# amplifier_only_clean.net
KiCad netlist of a schematic drawn in EAGLE
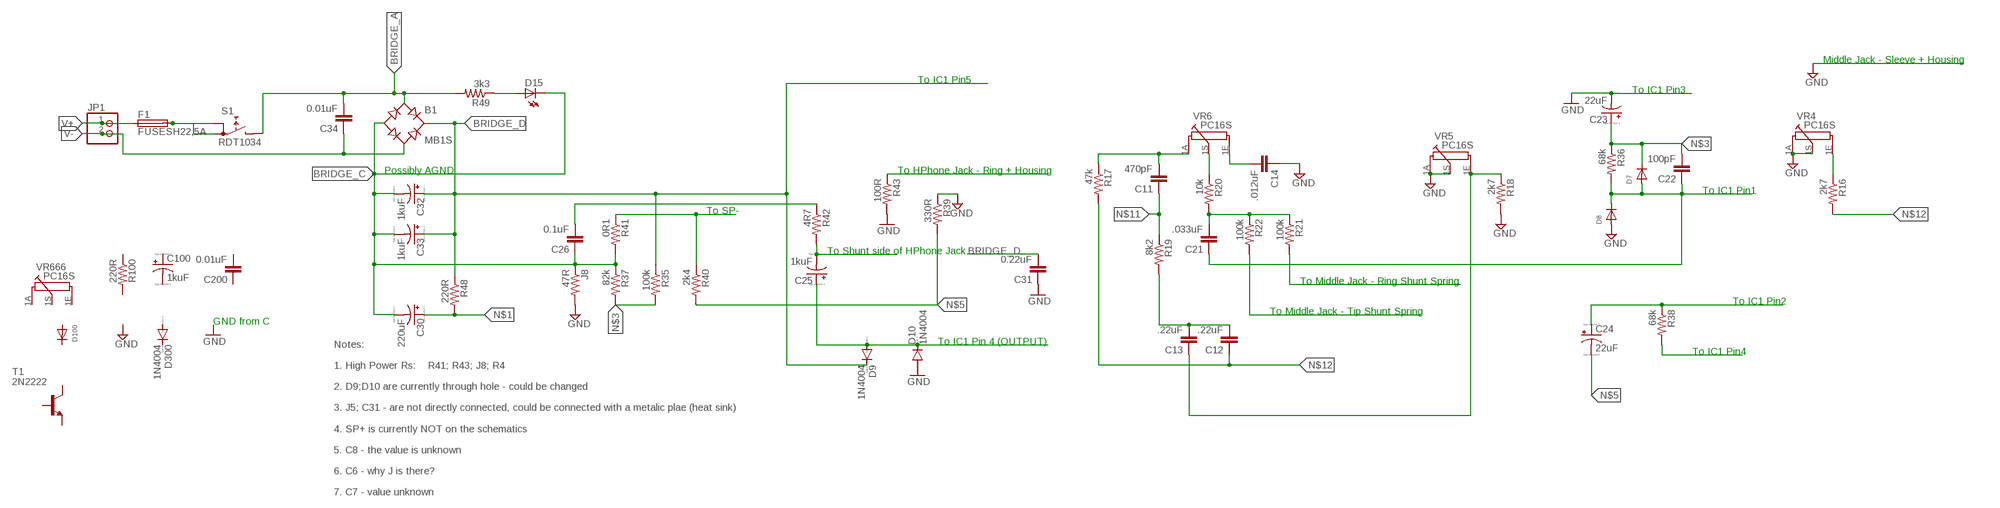
[diagram p0: schematic, sheet 1, part 1 of 2]
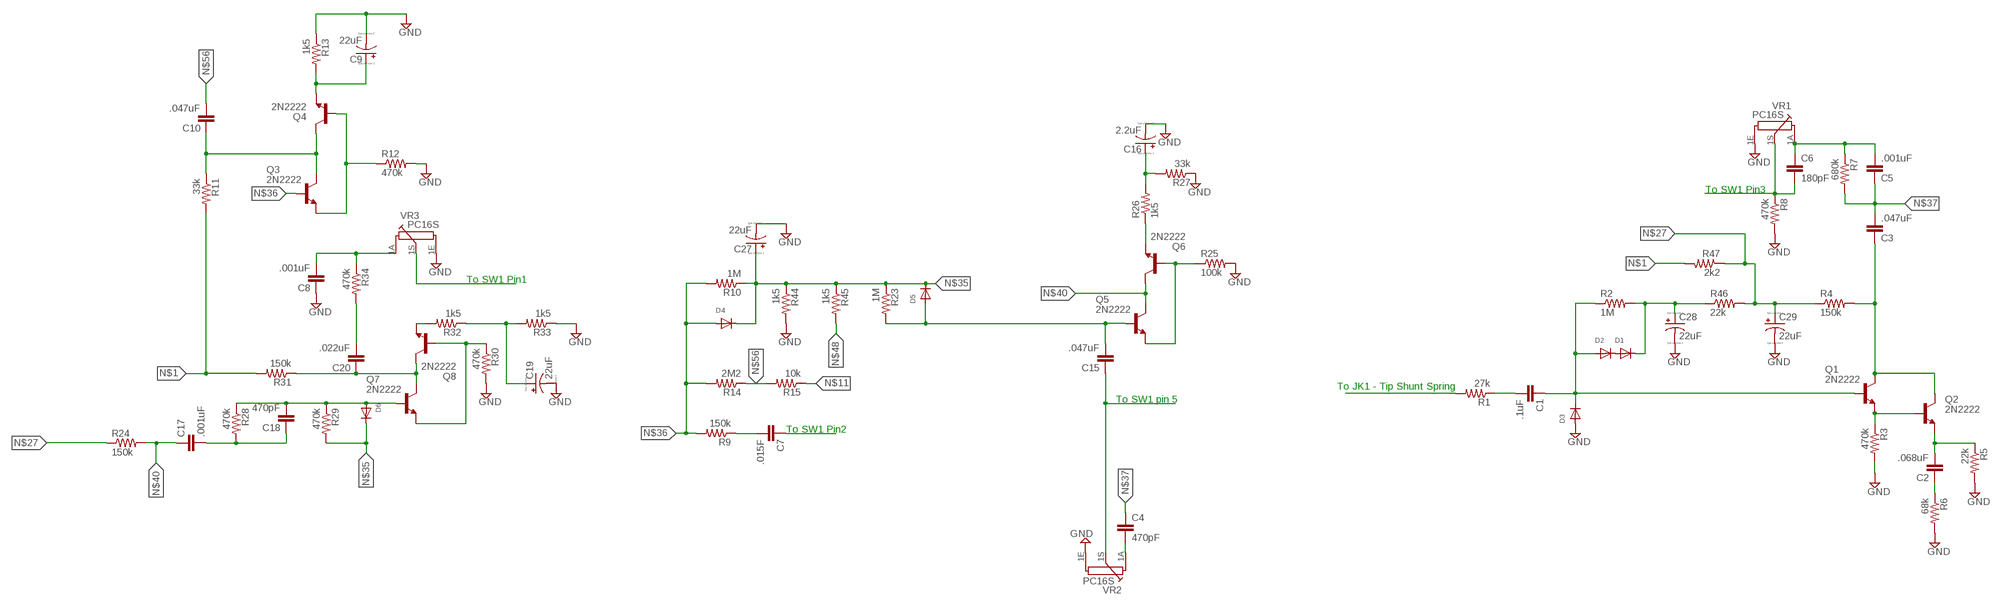
[diagram p1: schematic, sheet 1, part 2 of 2]

(export (version "E")
  (design (tool "Eeschema 10.0.6"))
  (components
    (comp (ref "B1")
      (value "MB1S")
      (footprint "eagle-import:SOIC-4")
      (libsource (lib "eagle-import") (part "MBS1"))
    )
    (comp (ref "C1")
      (value ".1uF")
      (footprint "eagle-import:C0603")
      (libsource (lib "eagle-import") (part "C-EUC0603"))
    )
    (comp (ref "C2")
      (value ".068uF")
      (footprint "eagle-import:C0603")
      (libsource (lib "eagle-import") (part "C-EUC0603"))
    )
    (comp (ref "C3")
      (value ".047uF")
      (footprint "eagle-import:C0603")
      (libsource (lib "eagle-import") (part "C-EUC0603"))
    )
    (comp (ref "C4")
      (value "470pF")
      (footprint "eagle-import:C0603")
      (libsource (lib "eagle-import") (part "C-EUC0603"))
    )
    (comp (ref "C5")
      (value ".001uF")
      (footprint "eagle-import:C0603")
      (libsource (lib "eagle-import") (part "C-EUC0603"))
    )
    (comp (ref "C6")
      (value "180pF")
      (footprint "eagle-import:C0603")
      (libsource (lib "eagle-import") (part "C-EUC0603"))
    )
    (comp (ref "C7")
      (value ".015F")
      (footprint "eagle-import:C0603")
      (libsource (lib "eagle-import") (part "C-EUC0603"))
    )
    (comp (ref "C8")
      (value ".001uF")
      (footprint "eagle-import:C0603")
      (libsource (lib "eagle-import") (part "C-EUC0603"))
    )
    (comp (ref "C9")
      (value "22uF")
      (footprint "eagle-import:EB30D")
      (libsource (lib "eagle-import") (part "CPOL-USE10-30"))
    )
    (comp (ref "C10")
      (value ".047uF")
      (footprint "eagle-import:C0603")
      (libsource (lib "eagle-import") (part "C-EUC0603"))
    )
    (comp (ref "C11")
      (value "470pF")
      (footprint "eagle-import:C0603")
      (libsource (lib "eagle-import") (part "C-EUC0603"))
    )
    (comp (ref "C12")
      (value ".22uF")
      (footprint "eagle-import:C0603")
      (libsource (lib "eagle-import") (part "C-EUC0603"))
    )
    (comp (ref "C13")
      (value ".22uF")
      (footprint "eagle-import:C0603")
      (libsource (lib "eagle-import") (part "C-EUC0603"))
    )
    (comp (ref "C14")
      (value ".012uF")
      (footprint "eagle-import:C0603")
      (libsource (lib "eagle-import") (part "C-EUC0603"))
    )
    (comp (ref "C15")
      (value ".047uF")
      (footprint "eagle-import:C0603")
      (libsource (lib "eagle-import") (part "C-EUC0603"))
    )
    (comp (ref "C16")
      (value "2.2uF")
      (footprint "eagle-import:EB30D")
      (libsource (lib "eagle-import") (part "CPOL-USE10-30"))
    )
    (comp (ref "C17")
      (value ".001uF")
      (footprint "eagle-import:C0603")
      (libsource (lib "eagle-import") (part "C-EUC0603"))
    )
    (comp (ref "C18")
      (value "470pF")
      (footprint "eagle-import:C0603")
      (libsource (lib "eagle-import") (part "C-EUC0603"))
    )
    (comp (ref "C19")
      (value "22uF")
      (footprint "eagle-import:EB30D")
      (libsource (lib "eagle-import") (part "CPOL-USE10-30"))
    )
    (comp (ref "C20")
      (value ".022uF")
      (footprint "eagle-import:C0603")
      (libsource (lib "eagle-import") (part "C-EUC0603"))
    )
    (comp (ref "C21")
      (value ".033uF")
      (footprint "eagle-import:C0603")
      (libsource (lib "eagle-import") (part "C-EUC0603"))
    )
    (comp (ref "C22")
      (value "100pF")
      (footprint "eagle-import:C0603")
      (libsource (lib "eagle-import") (part "C-EUC0603"))
    )
    (comp (ref "C23")
      (value "22uF")
      (footprint "eagle-import:EB30D")
      (libsource (lib "eagle-import") (part "CPOL-USE10-30"))
    )
    (comp (ref "C24")
      (value "22uF")
      (footprint "eagle-import:EB30D")
      (libsource (lib "eagle-import") (part "CPOL-USE10-30"))
    )
    (comp (ref "C25")
      (value "1kuF")
      (footprint "eagle-import:EB30D")
      (libsource (lib "eagle-import") (part "CPOL-USE10-30"))
    )
    (comp (ref "C26")
      (value "0.1uF")
      (footprint "eagle-import:C0603")
      (libsource (lib "eagle-import") (part "C-EUC0603"))
    )
    (comp (ref "C27")
      (value "22uF")
      (footprint "eagle-import:EB30D")
      (libsource (lib "eagle-import") (part "CPOL-USE10-30"))
    )
    (comp (ref "C28")
      (value "22uF")
      (footprint "eagle-import:EB30D")
      (libsource (lib "eagle-import") (part "CPOL-USE10-30"))
    )
    (comp (ref "C29")
      (value "22uF")
      (footprint "eagle-import:EB30D")
      (libsource (lib "eagle-import") (part "CPOL-USE10-30"))
    )
    (comp (ref "C30")
      (value "220uF")
      (footprint "eagle-import:E3,5-8")
      (libsource (lib "eagle-import") (part "CPOL-USE3.5-8"))
    )
    (comp (ref "C31")
      (value "0.22uF")
      (footprint "eagle-import:C0603")
      (libsource (lib "eagle-import") (part "C-EUC0603"))
    )
    (comp (ref "C32")
      (value "1kuF")
      (footprint "eagle-import:EB30D")
      (libsource (lib "eagle-import") (part "CPOL-USE10-30"))
    )
    (comp (ref "C33")
      (value "1kuF")
      (footprint "eagle-import:EB30D")
      (libsource (lib "eagle-import") (part "CPOL-USE10-30"))
    )
    (comp (ref "C34")
      (value "0.01uF")
      (footprint "eagle-import:C0603")
      (libsource (lib "eagle-import") (part "C-EUC0603"))
    )
    (comp (ref "C100")
      (value "1kuF")
      (footprint "eagle-import:EB30D")
      (libsource (lib "eagle-import") (part "CPOL-USE10-30"))
    )
    (comp (ref "C200")
      (value "0.01uF")
      (footprint "eagle-import:C0603")
      (libsource (lib "eagle-import") (part "C-EUC0603"))
    )
    (comp (ref "D1")
      (value "DIODESOD-323F")
      (footprint "eagle-import:SOD-323F")
      (libsource (lib "eagle-import") (part "DIODESOD-323F"))
    )
    (comp (ref "D2")
      (value "DIODESOD-323F")
      (footprint "eagle-import:SOD-323F")
      (libsource (lib "eagle-import") (part "DIODESOD-323F"))
    )
    (comp (ref "D3")
      (value "DIODESOD-323F")
      (footprint "eagle-import:SOD-323F")
      (libsource (lib "eagle-import") (part "DIODESOD-323F"))
    )
    (comp (ref "D4")
      (value "DIODESOD-323F")
      (footprint "eagle-import:SOD-323F")
      (libsource (lib "eagle-import") (part "DIODESOD-323F"))
    )
    (comp (ref "D5")
      (value "DIODESOD-323F")
      (footprint "eagle-import:SOD-323F")
      (libsource (lib "eagle-import") (part "DIODESOD-323F"))
    )
    (comp (ref "D6")
      (value "DIODESOD-323F")
      (footprint "eagle-import:SOD-323F")
      (libsource (lib "eagle-import") (part "DIODESOD-323F"))
    )
    (comp (ref "D7")
      (value "DIODESOD-323F")
      (footprint "eagle-import:SOD-323F")
      (libsource (lib "eagle-import") (part "DIODESOD-323F"))
    )
    (comp (ref "D8")
      (value "DIODESOD-323F")
      (footprint "eagle-import:SOD-323F")
      (libsource (lib "eagle-import") (part "DIODESOD-323F"))
    )
    (comp (ref "D9")
      (value "1N4004")
      (footprint "eagle-import:DO41-10")
      (libsource (lib "eagle-import") (part "1N4004"))
    )
    (comp (ref "D10")
      (value "1N4004")
      (footprint "eagle-import:DO41-10")
      (libsource (lib "eagle-import") (part "1N4004"))
    )
    (comp (ref "D15")
      (value "LEDCHIP-LED0603")
      (footprint "eagle-import:CHIP-LED0603")
      (libsource (lib "eagle-import") (part "LEDCHIP-LED0603"))
    )
    (comp (ref "D100")
      (value "DIODESOD-323F")
      (footprint "eagle-import:SOD-323F")
      (libsource (lib "eagle-import") (part "DIODESOD-323F"))
    )
    (comp (ref "D300")
      (value "1N4004")
      (footprint "eagle-import:DO41-10")
      (libsource (lib "eagle-import") (part "1N4004"))
    )
    (comp (ref "F1")
      (value "FUSESH22,5A")
      (footprint "eagle-import:SH22,5A")
      (libsource (lib "eagle-import") (part "FUSESH22,5A"))
    )
    (comp (ref "J8")
      (value "47R")
      (footprint "eagle-import:R0603")
      (libsource (lib "eagle-import") (part "R-US_R0603"))
    )
    (comp (ref "JP1")
      (value "PINHD-1X2")
      (footprint "eagle-import:1X02")
      (libsource (lib "eagle-import") (part "PINHD-1X2"))
    )
    (comp (ref "Q1")
      (value "2N2222")
      (footprint "eagle-import:TO92-EBC-OVAL")
      (libsource (lib "eagle-import") (part "2N2222"))
    )
    (comp (ref "Q2")
      (value "2N2222")
      (footprint "eagle-import:TO92-EBC-OVAL")
      (libsource (lib "eagle-import") (part "2N2222"))
    )
    (comp (ref "Q3")
      (value "2N2222")
      (footprint "eagle-import:TO92-EBC-OVAL")
      (libsource (lib "eagle-import") (part "2N2222"))
    )
    (comp (ref "Q4")
      (value "2N2222")
      (footprint "eagle-import:TO92-EBC-OVAL")
      (libsource (lib "eagle-import") (part "2N2222"))
    )
    (comp (ref "Q5")
      (value "2N2222")
      (footprint "eagle-import:TO92-EBC-OVAL")
      (libsource (lib "eagle-import") (part "2N2222"))
    )
    (comp (ref "Q6")
      (value "2N2222")
      (footprint "eagle-import:TO92-EBC-OVAL")
      (libsource (lib "eagle-import") (part "2N2222"))
    )
    (comp (ref "Q7")
      (value "2N2222")
      (footprint "eagle-import:TO92-EBC-OVAL")
      (libsource (lib "eagle-import") (part "2N2222"))
    )
    (comp (ref "Q8")
      (value "2N2222")
      (footprint "eagle-import:TO92-EBC-OVAL")
      (libsource (lib "eagle-import") (part "2N2222"))
    )
    (comp (ref "R1")
      (value "27k")
      (footprint "eagle-import:R0603")
      (libsource (lib "eagle-import") (part "R-US_R0603"))
    )
    (comp (ref "R2")
      (value "1M")
      (footprint "eagle-import:R0603")
      (libsource (lib "eagle-import") (part "R-US_R0603"))
    )
    (comp (ref "R3")
      (value "470k")
      (footprint "eagle-import:R0603")
      (libsource (lib "eagle-import") (part "R-US_R0603"))
    )
    (comp (ref "R4")
      (value "150k")
      (footprint "eagle-import:R0603")
      (libsource (lib "eagle-import") (part "R-US_R0603"))
    )
    (comp (ref "R5")
      (value "22k")
      (footprint "eagle-import:R0603")
      (libsource (lib "eagle-import") (part "R-US_R0603"))
    )
    (comp (ref "R6")
      (value "68k")
      (footprint "eagle-import:R0603")
      (libsource (lib "eagle-import") (part "R-US_R0603"))
    )
    (comp (ref "R7")
      (value "680k")
      (footprint "eagle-import:R0603")
      (libsource (lib "eagle-import") (part "R-US_R0603"))
    )
    (comp (ref "R8")
      (value "470k")
      (footprint "eagle-import:R0603")
      (libsource (lib "eagle-import") (part "R-US_R0603"))
    )
    (comp (ref "R9")
      (value "150k")
      (footprint "eagle-import:R0603")
      (libsource (lib "eagle-import") (part "R-US_R0603"))
    )
    (comp (ref "R10")
      (value "1M")
      (footprint "eagle-import:R0603")
      (libsource (lib "eagle-import") (part "R-US_R0603"))
    )
    (comp (ref "R11")
      (value "33k")
      (footprint "eagle-import:R0603")
      (libsource (lib "eagle-import") (part "R-US_R0603"))
    )
    (comp (ref "R12")
      (value "470k")
      (footprint "eagle-import:R0603")
      (libsource (lib "eagle-import") (part "R-US_R0603"))
    )
    (comp (ref "R13")
      (value "1k5")
      (footprint "eagle-import:R0603")
      (libsource (lib "eagle-import") (part "R-US_R0603"))
    )
    (comp (ref "R14")
      (value "2M2")
      (footprint "eagle-import:R0603")
      (libsource (lib "eagle-import") (part "R-US_R0603"))
    )
    (comp (ref "R15")
      (value "10k")
      (footprint "eagle-import:R0603")
      (libsource (lib "eagle-import") (part "R-US_R0603"))
    )
    (comp (ref "R16")
      (value "2k7")
      (footprint "eagle-import:R0603")
      (libsource (lib "eagle-import") (part "R-US_R0603"))
    )
    (comp (ref "R17")
      (value "47k")
      (footprint "eagle-import:R0603")
      (libsource (lib "eagle-import") (part "R-US_R0603"))
    )
    (comp (ref "R18")
      (value "2k7")
      (footprint "eagle-import:R0603")
      (libsource (lib "eagle-import") (part "R-US_R0603"))
    )
    (comp (ref "R19")
      (value "8k2")
      (footprint "eagle-import:R0603")
      (libsource (lib "eagle-import") (part "R-US_R0603"))
    )
    (comp (ref "R20")
      (value "10k")
      (footprint "eagle-import:R0603")
      (libsource (lib "eagle-import") (part "R-US_R0603"))
    )
    (comp (ref "R21")
      (value "100k")
      (footprint "eagle-import:R0603")
      (libsource (lib "eagle-import") (part "R-US_R0603"))
    )
    (comp (ref "R22")
      (value "100k")
      (footprint "eagle-import:R0603")
      (libsource (lib "eagle-import") (part "R-US_R0603"))
    )
    (comp (ref "R23")
      (value "1M")
      (footprint "eagle-import:R0603")
      (libsource (lib "eagle-import") (part "R-US_R0603"))
    )
    (comp (ref "R24")
      (value "150k")
      (footprint "eagle-import:R0603")
      (libsource (lib "eagle-import") (part "R-US_R0603"))
    )
    (comp (ref "R25")
      (value "100k")
      (footprint "eagle-import:R0603")
      (libsource (lib "eagle-import") (part "R-US_R0603"))
    )
    (comp (ref "R26")
      (value "1k5")
      (footprint "eagle-import:R0603")
      (libsource (lib "eagle-import") (part "R-US_R0603"))
    )
    (comp (ref "R27")
      (value "33k")
      (footprint "eagle-import:R0603")
      (libsource (lib "eagle-import") (part "R-US_R0603"))
    )
    (comp (ref "R28")
      (value "470k")
      (footprint "eagle-import:R0603")
      (libsource (lib "eagle-import") (part "R-US_R0603"))
    )
    (comp (ref "R29")
      (value "470k")
      (footprint "eagle-import:R0603")
      (libsource (lib "eagle-import") (part "R-US_R0603"))
    )
    (comp (ref "R30")
      (value "470k")
      (footprint "eagle-import:R0603")
      (libsource (lib "eagle-import") (part "R-US_R0603"))
    )
    (comp (ref "R31")
      (value "150k")
      (footprint "eagle-import:R0603")
      (libsource (lib "eagle-import") (part "R-US_R0603"))
    )
    (comp (ref "R32")
      (value "1k5")
      (footprint "eagle-import:R0603")
      (libsource (lib "eagle-import") (part "R-US_R0603"))
    )
    (comp (ref "R33")
      (value "1k5")
      (footprint "eagle-import:R0603")
      (libsource (lib "eagle-import") (part "R-US_R0603"))
    )
    (comp (ref "R34")
      (value "470k")
      (footprint "eagle-import:R0603")
      (libsource (lib "eagle-import") (part "R-US_R0603"))
    )
    (comp (ref "R35")
      (value "100k")
      (footprint "eagle-import:R0603")
      (libsource (lib "eagle-import") (part "R-US_R0603"))
    )
    (comp (ref "R36")
      (value "68k")
      (footprint "eagle-import:R0603")
      (libsource (lib "eagle-import") (part "R-US_R0603"))
    )
    (comp (ref "R37")
      (value "82k")
      (footprint "eagle-import:R0603")
      (libsource (lib "eagle-import") (part "R-US_R0603"))
    )
    (comp (ref "R38")
      (value "68k")
      (footprint "eagle-import:R0603")
      (libsource (lib "eagle-import") (part "R-US_R0603"))
    )
    (comp (ref "R39")
      (value "330R")
      (footprint "eagle-import:R0603")
      (libsource (lib "eagle-import") (part "R-US_R0603"))
    )
    (comp (ref "R40")
      (value "2k4")
      (footprint "eagle-import:R0603")
      (libsource (lib "eagle-import") (part "R-US_R0603"))
    )
    (comp (ref "R41")
      (value "0R1")
      (footprint "eagle-import:R0603")
      (libsource (lib "eagle-import") (part "R-US_R0603"))
    )
    (comp (ref "R42")
      (value "4R7")
      (footprint "eagle-import:R0603")
      (libsource (lib "eagle-import") (part "R-US_R0603"))
    )
    (comp (ref "R43")
      (value "100R")
      (footprint "eagle-import:R0603")
      (libsource (lib "eagle-import") (part "R-US_R0603"))
    )
    (comp (ref "R44")
      (value "1k5")
      (footprint "eagle-import:R0603")
      (libsource (lib "eagle-import") (part "R-US_R0603"))
    )
    (comp (ref "R45")
      (value "1k5")
      (footprint "eagle-import:R0603")
      (libsource (lib "eagle-import") (part "R-US_R0603"))
    )
    (comp (ref "R46")
      (value "22k")
      (footprint "eagle-import:R0603")
      (libsource (lib "eagle-import") (part "R-US_R0603"))
    )
    (comp (ref "R47")
      (value "2k2")
      (footprint "eagle-import:R0603")
      (libsource (lib "eagle-import") (part "R-US_R0603"))
    )
    (comp (ref "R48")
      (value "220R")
      (footprint "eagle-import:R0603")
      (libsource (lib "eagle-import") (part "R-US_R0603"))
    )
    (comp (ref "R49")
      (value "3k3")
      (footprint "eagle-import:R0603")
      (libsource (lib "eagle-import") (part "R-US_R0603"))
    )
    (comp (ref "R100")
      (value "220R")
      (footprint "eagle-import:R0603")
      (libsource (lib "eagle-import") (part "R-US_R0603"))
    )
    (comp (ref "S1")
      (value "RDT1034")
      (footprint "eagle-import:RDT1034")
      (libsource (lib "eagle-import") (part "RDT1034"))
    )
    (comp (ref "T1")
      (value "2N2222")
      (footprint "eagle-import:TO92-EBC-OVAL")
      (libsource (lib "eagle-import") (part "2N2222"))
    )
    (comp (ref "VR1")
      (value "PC16S")
      (footprint "eagle-import:PC16S")
      (libsource (lib "eagle-import") (part "PC16S"))
    )
    (comp (ref "VR2")
      (value "PC16S")
      (footprint "eagle-import:PC16S")
      (libsource (lib "eagle-import") (part "PC16S"))
    )
    (comp (ref "VR3")
      (value "PC16S")
      (footprint "eagle-import:PC16S")
      (libsource (lib "eagle-import") (part "PC16S"))
    )
    (comp (ref "VR4")
      (value "PC16S")
      (footprint "eagle-import:PC16S")
      (libsource (lib "eagle-import") (part "PC16S"))
    )
    (comp (ref "VR5")
      (value "PC16S")
      (footprint "eagle-import:PC16S")
      (libsource (lib "eagle-import") (part "PC16S"))
    )
    (comp (ref "VR6")
      (value "PC16S")
      (footprint "eagle-import:PC16S")
      (libsource (lib "eagle-import") (part "PC16S"))
    )
    (comp (ref "VR666")
      (value "PC16S")
      (footprint "eagle-import:PC16S")
      (libsource (lib "eagle-import") (part "PC16S"))
    )
  )
  (nets
    (net (code "1") (name "BRIDGE_A") (class "Default")
      (node (ref "B1") (pin "~1") (pinfunction "AC1_~1") (pintype "passive"))
      (node (ref "C34") (pin "2") (pinfunction "2_2") (pintype "passive"))
      (node (ref "R49") (pin "2") (pinfunction "2_2") (pintype "passive"))
      (node (ref "S1") (pin "B") (pinfunction "B_B") (pintype "passive"))
    )
    (net (code "2") (name "BRIDGE_C") (class "Default")
      (node (ref "B1") (pin "-") (pinfunction "-_-") (pintype "passive"))
      (node (ref "C26") (pin "1") (pinfunction "1_1") (pintype "passive"))
      (node (ref "C30") (pin "-") (pinfunction "-_-") (pintype "passive"))
      (node (ref "C32") (pin "-") (pinfunction "-_-") (pintype "passive"))
      (node (ref "C33") (pin "-") (pinfunction "-_-") (pintype "passive"))
      (node (ref "D15") (pin "C") (pinfunction "C_C") (pintype "passive"))
      (node (ref "J8") (pin "1") (pinfunction "1_1") (pintype "passive"))
      (node (ref "R37") (pin "1") (pinfunction "1_1") (pintype "passive"))
      (node (ref "R41") (pin "2") (pinfunction "2_2") (pintype "passive"))
    )
    (net (code "3") (name "BRIDGE_D") (class "Default")
      (node (ref "B1") (pin "+") (pinfunction "+_+") (pintype "passive"))
      (node (ref "C31") (pin "2") (pinfunction "2_2") (pintype "passive"))
      (node (ref "C32") (pin "+") (pinfunction "+_+") (pintype "passive"))
      (node (ref "C33") (pin "+") (pinfunction "+_+") (pintype "passive"))
      (node (ref "D9") (pin "C") (pinfunction "C_C") (pintype "passive"))
      (node (ref "R35") (pin "1") (pinfunction "1_1") (pintype "passive"))
      (node (ref "R48") (pin "1") (pinfunction "1_1") (pintype "passive"))
    )
    (net (code "4") (name "GND") (class "Default")
      (node (ref "C14") (pin "1") (pinfunction "1_1") (pintype "passive"))
      (node (ref "C16") (pin "-") (pinfunction "-_-") (pintype "passive"))
      (node (ref "C19") (pin "-") (pinfunction "-_-") (pintype "passive"))
      (node (ref "C23") (pin "-") (pinfunction "-_-") (pintype "passive"))
      (node (ref "C27") (pin "-") (pinfunction "-_-") (pintype "passive"))
      (node (ref "C28") (pin "-") (pinfunction "-_-") (pintype "passive"))
      (node (ref "C29") (pin "-") (pinfunction "-_-") (pintype "passive"))
      (node (ref "C31") (pin "1") (pinfunction "1_1") (pintype "passive"))
      (node (ref "C8") (pin "1") (pinfunction "1_1") (pintype "passive"))
      (node (ref "C9") (pin "-") (pinfunction "-_-") (pintype "passive"))
      (node (ref "D10") (pin "A") (pinfunction "A_A") (pintype "passive"))
      (node (ref "D3") (pin "A") (pinfunction "A_A") (pintype "passive"))
      (node (ref "D8") (pin "A") (pinfunction "A_A") (pintype "passive"))
      (node (ref "J8") (pin "2") (pinfunction "2_2") (pintype "passive"))
      (node (ref "R12") (pin "2") (pinfunction "2_2") (pintype "passive"))
      (node (ref "R13") (pin "1") (pinfunction "1_1") (pintype "passive"))
      (node (ref "R18") (pin "2") (pinfunction "2_2") (pintype "passive"))
      (node (ref "R25") (pin "2") (pinfunction "2_2") (pintype "passive"))
      (node (ref "R27") (pin "1") (pinfunction "1_1") (pintype "passive"))
      (node (ref "R3") (pin "2") (pinfunction "2_2") (pintype "passive"))
      (node (ref "R30") (pin "2") (pinfunction "2_2") (pintype "passive"))
      (node (ref "R33") (pin "1") (pinfunction "1_1") (pintype "passive"))
      (node (ref "R39") (pin "1") (pinfunction "1_1") (pintype "passive"))
      (node (ref "R43") (pin "2") (pinfunction "2_2") (pintype "passive"))
      (node (ref "R44") (pin "2") (pinfunction "2_2") (pintype "passive"))
      (node (ref "R5") (pin "2") (pinfunction "2_2") (pintype "passive"))
      (node (ref "R6") (pin "2") (pinfunction "2_2") (pintype "passive"))
      (node (ref "R8") (pin "2") (pinfunction "2_2") (pintype "passive"))
      (node (ref "VR1") (pin "1E") (pinfunction "1E_1E") (pintype "passive"))
      (node (ref "VR2") (pin "1E") (pinfunction "1E_1E") (pintype "passive"))
      (node (ref "VR3") (pin "1E") (pinfunction "1E_1E") (pintype "passive"))
      (node (ref "VR4") (pin "1A") (pinfunction "1A_1A") (pintype "passive"))
      (node (ref "VR4") (pin "1S") (pinfunction "1S_1S") (pintype "passive"))
      (node (ref "VR5") (pin "1A") (pinfunction "1A_1A") (pintype "passive"))
      (node (ref "VR5") (pin "1S") (pinfunction "1S_1S") (pintype "passive"))
    )
    (net (code "5") (name "N$1") (class "Default")
      (node (ref "C30") (pin "+") (pinfunction "+_+") (pintype "passive"))
      (node (ref "R11") (pin "2") (pinfunction "2_2") (pintype "passive"))
      (node (ref "R31") (pin "2") (pinfunction "2_2") (pintype "passive"))
      (node (ref "R47") (pin "2") (pinfunction "2_2") (pintype "passive"))
      (node (ref "R48") (pin "2") (pinfunction "2_2") (pintype "passive"))
    )
    (net (code "6") (name "N$3") (class "Default")
      (node (ref "C22") (pin "2") (pinfunction "2_2") (pintype "passive"))
      (node (ref "C23") (pin "+") (pinfunction "+_+") (pintype "passive"))
      (node (ref "D7") (pin "C") (pinfunction "C_C") (pintype "passive"))
      (node (ref "R35") (pin "2") (pinfunction "2_2") (pintype "passive"))
      (node (ref "R36") (pin "1") (pinfunction "1_1") (pintype "passive"))
      (node (ref "R37") (pin "2") (pinfunction "2_2") (pintype "passive"))
    )
    (net (code "7") (name "N$5") (class "Default")
      (node (ref "C24") (pin "-") (pinfunction "-_-") (pintype "passive"))
      (node (ref "R39") (pin "2") (pinfunction "2_2") (pintype "passive"))
      (node (ref "R40") (pin "2") (pinfunction "2_2") (pintype "passive"))
    )
    (net (code "8") (name "N$11") (class "Default")
      (node (ref "C11") (pin "1") (pinfunction "1_1") (pintype "passive"))
      (node (ref "R15") (pin "1") (pinfunction "1_1") (pintype "passive"))
      (node (ref "R19") (pin "1") (pinfunction "1_1") (pintype "passive"))
    )
    (net (code "9") (name "N$12") (class "Default")
      (node (ref "C12") (pin "1") (pinfunction "1_1") (pintype "passive"))
      (node (ref "R16") (pin "2") (pinfunction "2_2") (pintype "passive"))
      (node (ref "R17") (pin "2") (pinfunction "2_2") (pintype "passive"))
    )
    (net (code "10") (name "N$27") (class "Default")
      (node (ref "C29") (pin "+") (pinfunction "+_+") (pintype "passive"))
      (node (ref "R24") (pin "1") (pinfunction "1_1") (pintype "passive"))
      (node (ref "R4") (pin "1") (pinfunction "1_1") (pintype "passive"))
      (node (ref "R46") (pin "2") (pinfunction "2_2") (pintype "passive"))
      (node (ref "R47") (pin "1") (pinfunction "1_1") (pintype "passive"))
    )
    (net (code "11") (name "N$35") (class "Default")
      (node (ref "C27") (pin "+") (pinfunction "+_+") (pintype "passive"))
      (node (ref "D4") (pin "C") (pinfunction "C_C") (pintype "passive"))
      (node (ref "D5") (pin "C") (pinfunction "C_C") (pintype "passive"))
      (node (ref "D6") (pin "C") (pinfunction "C_C") (pintype "passive"))
      (node (ref "R10") (pin "1") (pinfunction "1_1") (pintype "passive"))
      (node (ref "R23") (pin "1") (pinfunction "1_1") (pintype "passive"))
      (node (ref "R29") (pin "2") (pinfunction "2_2") (pintype "passive"))
      (node (ref "R44") (pin "1") (pinfunction "1_1") (pintype "passive"))
      (node (ref "R45") (pin "1") (pinfunction "1_1") (pintype "passive"))
    )
    (net (code "12") (name "N$36") (class "Default")
      (node (ref "D4") (pin "A") (pinfunction "A_A") (pintype "passive"))
      (node (ref "Q3") (pin "B") (pinfunction "B_B") (pintype "passive"))
      (node (ref "R10") (pin "2") (pinfunction "2_2") (pintype "passive"))
      (node (ref "R14") (pin "2") (pinfunction "2_2") (pintype "passive"))
      (node (ref "R9") (pin "2") (pinfunction "2_2") (pintype "passive"))
    )
    (net (code "13") (name "N$37") (class "Default")
      (node (ref "C3") (pin "2") (pinfunction "2_2") (pintype "passive"))
      (node (ref "C4") (pin "1") (pinfunction "1_1") (pintype "passive"))
      (node (ref "C5") (pin "1") (pinfunction "1_1") (pintype "passive"))
      (node (ref "R7") (pin "2") (pinfunction "2_2") (pintype "passive"))
    )
    (net (code "14") (name "N$40") (class "Default")
      (node (ref "C17") (pin "1") (pinfunction "1_1") (pintype "passive"))
      (node (ref "Q5") (pin "C") (pinfunction "C_C") (pintype "passive"))
      (node (ref "Q6") (pin "C") (pinfunction "C_C") (pintype "passive"))
      (node (ref "R24") (pin "2") (pinfunction "2_2") (pintype "passive"))
    )
    (net (code "15") (name "N$48") (class "Default")
      (node (ref "R45") (pin "2") (pinfunction "2_2") (pintype "passive"))
    )
    (net (code "16") (name "N$56") (class "Default")
      (node (ref "C10") (pin "2") (pinfunction "2_2") (pintype "passive"))
      (node (ref "R14") (pin "1") (pinfunction "1_1") (pintype "passive"))
      (node (ref "R15") (pin "2") (pinfunction "2_2") (pintype "passive"))
    )
    (net (code "17") (name "Net-(C1-Pad1)") (class "Default")
      (node (ref "C1") (pin "1") (pinfunction "1_1") (pintype "passive"))
      (node (ref "D2") (pin "A") (pinfunction "A_A") (pintype "passive"))
      (node (ref "D3") (pin "C") (pinfunction "C_C") (pintype "passive"))
      (node (ref "Q1") (pin "B") (pinfunction "B_B") (pintype "passive"))
      (node (ref "R2") (pin "1") (pinfunction "1_1") (pintype "passive"))
    )
    (net (code "18") (name "Net-(C1-Pad2)") (class "Default")
      (node (ref "C1") (pin "2") (pinfunction "2_2") (pintype "passive"))
      (node (ref "R1") (pin "1") (pinfunction "1_1") (pintype "passive"))
    )
    (net (code "19") (name "Net-(C2-Pad1)") (class "Default")
      (node (ref "C2") (pin "1") (pinfunction "1_1") (pintype "passive"))
      (node (ref "R6") (pin "1") (pinfunction "1_1") (pintype "passive"))
    )
    (net (code "20") (name "Net-(C2-Pad2)") (class "Default")
      (node (ref "C2") (pin "2") (pinfunction "2_2") (pintype "passive"))
      (node (ref "Q2") (pin "E") (pinfunction "E_E") (pintype "passive"))
      (node (ref "R5") (pin "1") (pinfunction "1_1") (pintype "passive"))
    )
    (net (code "21") (name "Net-(C3-Pad1)") (class "Default")
      (node (ref "C3") (pin "1") (pinfunction "1_1") (pintype "passive"))
      (node (ref "Q1") (pin "C") (pinfunction "C_C") (pintype "passive"))
      (node (ref "Q2") (pin "C") (pinfunction "C_C") (pintype "passive"))
      (node (ref "R4") (pin "2") (pinfunction "2_2") (pintype "passive"))
    )
    (net (code "22") (name "Net-(C4-Pad2)") (class "Default")
      (node (ref "C4") (pin "2") (pinfunction "2_2") (pintype "passive"))
      (node (ref "VR2") (pin "1A") (pinfunction "1A_1A") (pintype "passive"))
    )
    (net (code "23") (name "Net-(C5-Pad2)") (class "Default")
      (node (ref "C5") (pin "2") (pinfunction "2_2") (pintype "passive"))
      (node (ref "C6") (pin "2") (pinfunction "2_2") (pintype "passive"))
      (node (ref "R7") (pin "1") (pinfunction "1_1") (pintype "passive"))
      (node (ref "VR1") (pin "1A") (pinfunction "1A_1A") (pintype "passive"))
    )
    (net (code "24") (name "Net-(C6-Pad1)") (class "Default")
      (node (ref "C6") (pin "1") (pinfunction "1_1") (pintype "passive"))
      (node (ref "R8") (pin "1") (pinfunction "1_1") (pintype "passive"))
      (node (ref "VR1") (pin "1S") (pinfunction "1S_1S") (pintype "passive"))
    )
    (net (code "25") (name "Net-(C7-Pad2)") (class "Default")
      (node (ref "C7") (pin "2") (pinfunction "2_2") (pintype "passive"))
      (node (ref "R9") (pin "1") (pinfunction "1_1") (pintype "passive"))
    )
    (net (code "26") (name "Net-(C8-Pad2)") (class "Default")
      (node (ref "C8") (pin "2") (pinfunction "2_2") (pintype "passive"))
      (node (ref "R34") (pin "1") (pinfunction "1_1") (pintype "passive"))
      (node (ref "VR3") (pin "1A") (pinfunction "1A_1A") (pintype "passive"))
    )
    (net (code "27") (name "Net-(C9-Pad+)") (class "Default")
      (node (ref "C9") (pin "+") (pinfunction "+_+") (pintype "passive"))
      (node (ref "Q4") (pin "E") (pinfunction "E_E") (pintype "passive"))
      (node (ref "R13") (pin "2") (pinfunction "2_2") (pintype "passive"))
    )
    (net (code "28") (name "Net-(C10-Pad1)") (class "Default")
      (node (ref "C10") (pin "1") (pinfunction "1_1") (pintype "passive"))
      (node (ref "Q3") (pin "C") (pinfunction "C_C") (pintype "passive"))
      (node (ref "Q4") (pin "C") (pinfunction "C_C") (pintype "passive"))
      (node (ref "R11") (pin "1") (pinfunction "1_1") (pintype "passive"))
    )
    (net (code "29") (name "Net-(C11-Pad2)") (class "Default")
      (node (ref "C11") (pin "2") (pinfunction "2_2") (pintype "passive"))
      (node (ref "R17") (pin "1") (pinfunction "1_1") (pintype "passive"))
      (node (ref "VR6") (pin "1A") (pinfunction "1A_1A") (pintype "passive"))
    )
    (net (code "30") (name "Net-(C12-Pad2)") (class "Default")
      (node (ref "C12") (pin "2") (pinfunction "2_2") (pintype "passive"))
      (node (ref "C13") (pin "2") (pinfunction "2_2") (pintype "passive"))
      (node (ref "R19") (pin "2") (pinfunction "2_2") (pintype "passive"))
    )
    (net (code "31") (name "Net-(C13-Pad1)") (class "Default")
      (node (ref "C13") (pin "1") (pinfunction "1_1") (pintype "passive"))
      (node (ref "R18") (pin "1") (pinfunction "1_1") (pintype "passive"))
      (node (ref "VR5") (pin "1E") (pinfunction "1E_1E") (pintype "passive"))
    )
    (net (code "32") (name "Net-(C14-Pad2)") (class "Default")
      (node (ref "C14") (pin "2") (pinfunction "2_2") (pintype "passive"))
      (node (ref "VR6") (pin "1E") (pinfunction "1E_1E") (pintype "passive"))
    )
    (net (code "33") (name "Net-(C15-Pad1)") (class "Default")
      (node (ref "C15") (pin "1") (pinfunction "1_1") (pintype "passive"))
      (node (ref "VR2") (pin "1S") (pinfunction "1S_1S") (pintype "passive"))
    )
    (net (code "34") (name "Net-(C15-Pad2)") (class "Default")
      (node (ref "C15") (pin "2") (pinfunction "2_2") (pintype "passive"))
      (node (ref "D5") (pin "A") (pinfunction "A_A") (pintype "passive"))
      (node (ref "Q5") (pin "B") (pinfunction "B_B") (pintype "passive"))
      (node (ref "R23") (pin "2") (pinfunction "2_2") (pintype "passive"))
    )
    (net (code "35") (name "Net-(C16-Pad+)") (class "Default")
      (node (ref "C16") (pin "+") (pinfunction "+_+") (pintype "passive"))
      (node (ref "R26") (pin "2") (pinfunction "2_2") (pintype "passive"))
      (node (ref "R27") (pin "2") (pinfunction "2_2") (pintype "passive"))
    )
    (net (code "36") (name "Net-(C17-Pad2)") (class "Default")
      (node (ref "C17") (pin "2") (pinfunction "2_2") (pintype "passive"))
      (node (ref "C18") (pin "1") (pinfunction "1_1") (pintype "passive"))
      (node (ref "R28") (pin "2") (pinfunction "2_2") (pintype "passive"))
    )
    (net (code "37") (name "Net-(C18-Pad2)") (class "Default")
      (node (ref "C18") (pin "2") (pinfunction "2_2") (pintype "passive"))
      (node (ref "D6") (pin "A") (pinfunction "A_A") (pintype "passive"))
      (node (ref "Q7") (pin "B") (pinfunction "B_B") (pintype "passive"))
      (node (ref "R28") (pin "1") (pinfunction "1_1") (pintype "passive"))
      (node (ref "R29") (pin "1") (pinfunction "1_1") (pintype "passive"))
    )
    (net (code "38") (name "Net-(C19-Pad+)") (class "Default")
      (node (ref "C19") (pin "+") (pinfunction "+_+") (pintype "passive"))
      (node (ref "R32") (pin "1") (pinfunction "1_1") (pintype "passive"))
      (node (ref "R33") (pin "2") (pinfunction "2_2") (pintype "passive"))
    )
    (net (code "39") (name "Net-(C20-Pad1)") (class "Default")
      (node (ref "C20") (pin "1") (pinfunction "1_1") (pintype "passive"))
      (node (ref "Q7") (pin "C") (pinfunction "C_C") (pintype "passive"))
      (node (ref "Q8") (pin "C") (pinfunction "C_C") (pintype "passive"))
      (node (ref "R31") (pin "1") (pinfunction "1_1") (pintype "passive"))
    )
    (net (code "40") (name "Net-(C20-Pad2)") (class "Default")
      (node (ref "C20") (pin "2") (pinfunction "2_2") (pintype "passive"))
      (node (ref "R34") (pin "2") (pinfunction "2_2") (pintype "passive"))
    )
    (net (code "41") (name "Net-(C21-Pad1)") (class "Default")
      (node (ref "C21") (pin "1") (pinfunction "1_1") (pintype "passive"))
      (node (ref "C22") (pin "1") (pinfunction "1_1") (pintype "passive"))
      (node (ref "D7") (pin "A") (pinfunction "A_A") (pintype "passive"))
      (node (ref "D8") (pin "C") (pinfunction "C_C") (pintype "passive"))
      (node (ref "R36") (pin "2") (pinfunction "2_2") (pintype "passive"))
    )
    (net (code "42") (name "Net-(C21-Pad2)") (class "Default")
      (node (ref "C21") (pin "2") (pinfunction "2_2") (pintype "passive"))
      (node (ref "R20") (pin "2") (pinfunction "2_2") (pintype "passive"))
      (node (ref "R21") (pin "1") (pinfunction "1_1") (pintype "passive"))
      (node (ref "R22") (pin "1") (pinfunction "1_1") (pintype "passive"))
    )
    (net (code "43") (name "Net-(C24-Pad+)") (class "Default")
      (node (ref "C24") (pin "+") (pinfunction "+_+") (pintype "passive"))
      (node (ref "R38") (pin "1") (pinfunction "1_1") (pintype "passive"))
    )
    (net (code "44") (name "Net-(C25-Pad+)") (class "Default")
      (node (ref "C25") (pin "+") (pinfunction "+_+") (pintype "passive"))
      (node (ref "D10") (pin "C") (pinfunction "C_C") (pintype "passive"))
      (node (ref "D9") (pin "A") (pinfunction "A_A") (pintype "passive"))
    )
    (net (code "45") (name "Net-(C25-Pad-)") (class "Default")
      (node (ref "C25") (pin "-") (pinfunction "-_-") (pintype "passive"))
      (node (ref "R42") (pin "2") (pinfunction "2_2") (pintype "passive"))
    )
    (net (code "46") (name "Net-(C26-Pad2)") (class "Default")
      (node (ref "C26") (pin "2") (pinfunction "2_2") (pintype "passive"))
      (node (ref "R42") (pin "1") (pinfunction "1_1") (pintype "passive"))
    )
    (net (code "47") (name "Net-(C28-Pad+)") (class "Default")
      (node (ref "C28") (pin "+") (pinfunction "+_+") (pintype "passive"))
      (node (ref "D1") (pin "C") (pinfunction "C_C") (pintype "passive"))
      (node (ref "R2") (pin "2") (pinfunction "2_2") (pintype "passive"))
      (node (ref "R46") (pin "1") (pinfunction "1_1") (pintype "passive"))
    )
    (net (code "48") (name "Net-(D1-PadA)") (class "Default")
      (node (ref "D1") (pin "A") (pinfunction "A_A") (pintype "passive"))
      (node (ref "D2") (pin "C") (pinfunction "C_C") (pintype "passive"))
    )
    (net (code "49") (name "Net-(D15-PadA)") (class "Default")
      (node (ref "D15") (pin "A") (pinfunction "A_A") (pintype "passive"))
      (node (ref "R49") (pin "1") (pinfunction "1_1") (pintype "passive"))
    )
    (net (code "50") (name "Net-(F1-Pad2)") (class "Default")
      (node (ref "F1") (pin "2") (pinfunction "2_2") (pintype "passive"))
      (node (ref "S1") (pin "A") (pinfunction "A_A") (pintype "passive"))
      (node (ref "S1") (pin "A1") (pinfunction "A1_A1") (pintype "passive"))
    )
    (net (code "51") (name "Net-(Q1-PadE)") (class "Default")
      (node (ref "Q1") (pin "E") (pinfunction "E_E") (pintype "passive"))
      (node (ref "Q2") (pin "B") (pinfunction "B_B") (pintype "passive"))
      (node (ref "R3") (pin "1") (pinfunction "1_1") (pintype "passive"))
    )
    (net (code "52") (name "Net-(Q3-PadE)") (class "Default")
      (node (ref "Q3") (pin "E") (pinfunction "E_E") (pintype "passive"))
      (node (ref "Q4") (pin "B") (pinfunction "B_B") (pintype "passive"))
      (node (ref "R12") (pin "1") (pinfunction "1_1") (pintype "passive"))
    )
    (net (code "53") (name "Net-(Q5-PadE)") (class "Default")
      (node (ref "Q5") (pin "E") (pinfunction "E_E") (pintype "passive"))
      (node (ref "Q6") (pin "B") (pinfunction "B_B") (pintype "passive"))
      (node (ref "R25") (pin "1") (pinfunction "1_1") (pintype "passive"))
    )
    (net (code "54") (name "Net-(Q6-PadE)") (class "Default")
      (node (ref "Q6") (pin "E") (pinfunction "E_E") (pintype "passive"))
      (node (ref "R26") (pin "1") (pinfunction "1_1") (pintype "passive"))
    )
    (net (code "55") (name "Net-(Q7-PadE)") (class "Default")
      (node (ref "Q7") (pin "E") (pinfunction "E_E") (pintype "passive"))
      (node (ref "Q8") (pin "B") (pinfunction "B_B") (pintype "passive"))
      (node (ref "R30") (pin "1") (pinfunction "1_1") (pintype "passive"))
    )
    (net (code "56") (name "Net-(Q8-PadE)") (class "Default")
      (node (ref "Q8") (pin "E") (pinfunction "E_E") (pintype "passive"))
      (node (ref "R32") (pin "2") (pinfunction "2_2") (pintype "passive"))
    )
    (net (code "57") (name "Net-(R16-Pad1)") (class "Default")
      (node (ref "R16") (pin "1") (pinfunction "1_1") (pintype "passive"))
      (node (ref "VR4") (pin "1E") (pinfunction "1E_1E") (pintype "passive"))
    )
    (net (code "58") (name "Net-(R20-Pad1)") (class "Default")
      (node (ref "R20") (pin "1") (pinfunction "1_1") (pintype "passive"))
      (node (ref "VR6") (pin "1S") (pinfunction "1S_1S") (pintype "passive"))
    )
    (net (code "59") (name "Net-(R40-Pad1)") (class "Default")
      (node (ref "R40") (pin "1") (pinfunction "1_1") (pintype "passive"))
      (node (ref "R41") (pin "1") (pinfunction "1_1") (pintype "passive"))
    )
    (net (code "60") (name "V+") (class "Default")
      (node (ref "F1") (pin "1") (pinfunction "1_1") (pintype "passive"))
      (node (ref "JP1") (pin "1") (pinfunction "1_1") (pintype "passive"))
    )
    (net (code "61") (name "V-") (class "Default")
      (node (ref "B1") (pin "~2") (pinfunction "AC2_~2") (pintype "passive"))
      (node (ref "C34") (pin "1") (pinfunction "1_1") (pintype "passive"))
      (node (ref "JP1") (pin "2") (pinfunction "2_2") (pintype "passive"))
    )
    (net (code "62") (name "unconnected-(C7-Pad1)") (class "Default")
      (node (ref "C7") (pin "1") (pinfunction "1_1") (pintype "passive"))
    )
    (net (code "63") (name "unconnected-(C100-Pad+)") (class "Default")
      (node (ref "C100") (pin "+") (pinfunction "+_+") (pintype "passive"))
    )
    (net (code "64") (name "unconnected-(C100-Pad-)") (class "Default")
      (node (ref "C100") (pin "-") (pinfunction "-_-") (pintype "passive"))
    )
    (net (code "65") (name "unconnected-(C200-Pad1)") (class "Default")
      (node (ref "C200") (pin "1") (pinfunction "1_1") (pintype "passive"))
    )
    (net (code "66") (name "unconnected-(C200-Pad2)") (class "Default")
      (node (ref "C200") (pin "2") (pinfunction "2_2") (pintype "passive"))
    )
    (net (code "67") (name "unconnected-(D100-PadA)") (class "Default")
      (node (ref "D100") (pin "A") (pinfunction "A_A") (pintype "passive"))
    )
    (net (code "68") (name "unconnected-(D100-PadC)") (class "Default")
      (node (ref "D100") (pin "C") (pinfunction "C_C") (pintype "passive"))
    )
    (net (code "69") (name "unconnected-(D300-PadA)") (class "Default")
      (node (ref "D300") (pin "A") (pinfunction "A_A") (pintype "passive"))
    )
    (net (code "70") (name "unconnected-(D300-PadC)") (class "Default")
      (node (ref "D300") (pin "C") (pinfunction "C_C") (pintype "passive"))
    )
    (net (code "71") (name "unconnected-(R1-Pad2)") (class "Default")
      (node (ref "R1") (pin "2") (pinfunction "2_2") (pintype "passive"))
    )
    (net (code "72") (name "unconnected-(R21-Pad2)") (class "Default")
      (node (ref "R21") (pin "2") (pinfunction "2_2") (pintype "passive"))
    )
    (net (code "73") (name "unconnected-(R22-Pad2)") (class "Default")
      (node (ref "R22") (pin "2") (pinfunction "2_2") (pintype "passive"))
    )
    (net (code "74") (name "unconnected-(R38-Pad2)") (class "Default")
      (node (ref "R38") (pin "2") (pinfunction "2_2") (pintype "passive"))
    )
    (net (code "75") (name "unconnected-(R43-Pad1)") (class "Default")
      (node (ref "R43") (pin "1") (pinfunction "1_1") (pintype "passive"))
    )
    (net (code "76") (name "unconnected-(R100-Pad1)") (class "Default")
      (node (ref "R100") (pin "1") (pinfunction "1_1") (pintype "passive"))
    )
    (net (code "77") (name "unconnected-(R100-Pad2)") (class "Default")
      (node (ref "R100") (pin "2") (pinfunction "2_2") (pintype "passive"))
    )
    (net (code "78") (name "unconnected-(T1-PadB)") (class "Default")
      (node (ref "T1") (pin "B") (pinfunction "B_B") (pintype "passive"))
    )
    (net (code "79") (name "unconnected-(T1-PadC)") (class "Default")
      (node (ref "T1") (pin "C") (pinfunction "C_C") (pintype "passive"))
    )
    (net (code "80") (name "unconnected-(T1-PadE)") (class "Default")
      (node (ref "T1") (pin "E") (pinfunction "E_E") (pintype "passive"))
    )
    (net (code "81") (name "unconnected-(VR3-Pad1S)") (class "Default")
      (node (ref "VR3") (pin "1S") (pinfunction "1S_1S") (pintype "passive"))
    )
    (net (code "82") (name "unconnected-(VR666-Pad1A)") (class "Default")
      (node (ref "VR666") (pin "1A") (pinfunction "1A_1A") (pintype "passive"))
    )
    (net (code "83") (name "unconnected-(VR666-Pad1E)") (class "Default")
      (node (ref "VR666") (pin "1E") (pinfunction "1E_1E") (pintype "passive"))
    )
    (net (code "84") (name "unconnected-(VR666-Pad1S)") (class "Default")
      (node (ref "VR666") (pin "1S") (pinfunction "1S_1S") (pintype "passive"))
    )
  )
)
